# Sheet2.net
KiCad netlist of a schematic drawn in Altium Designer
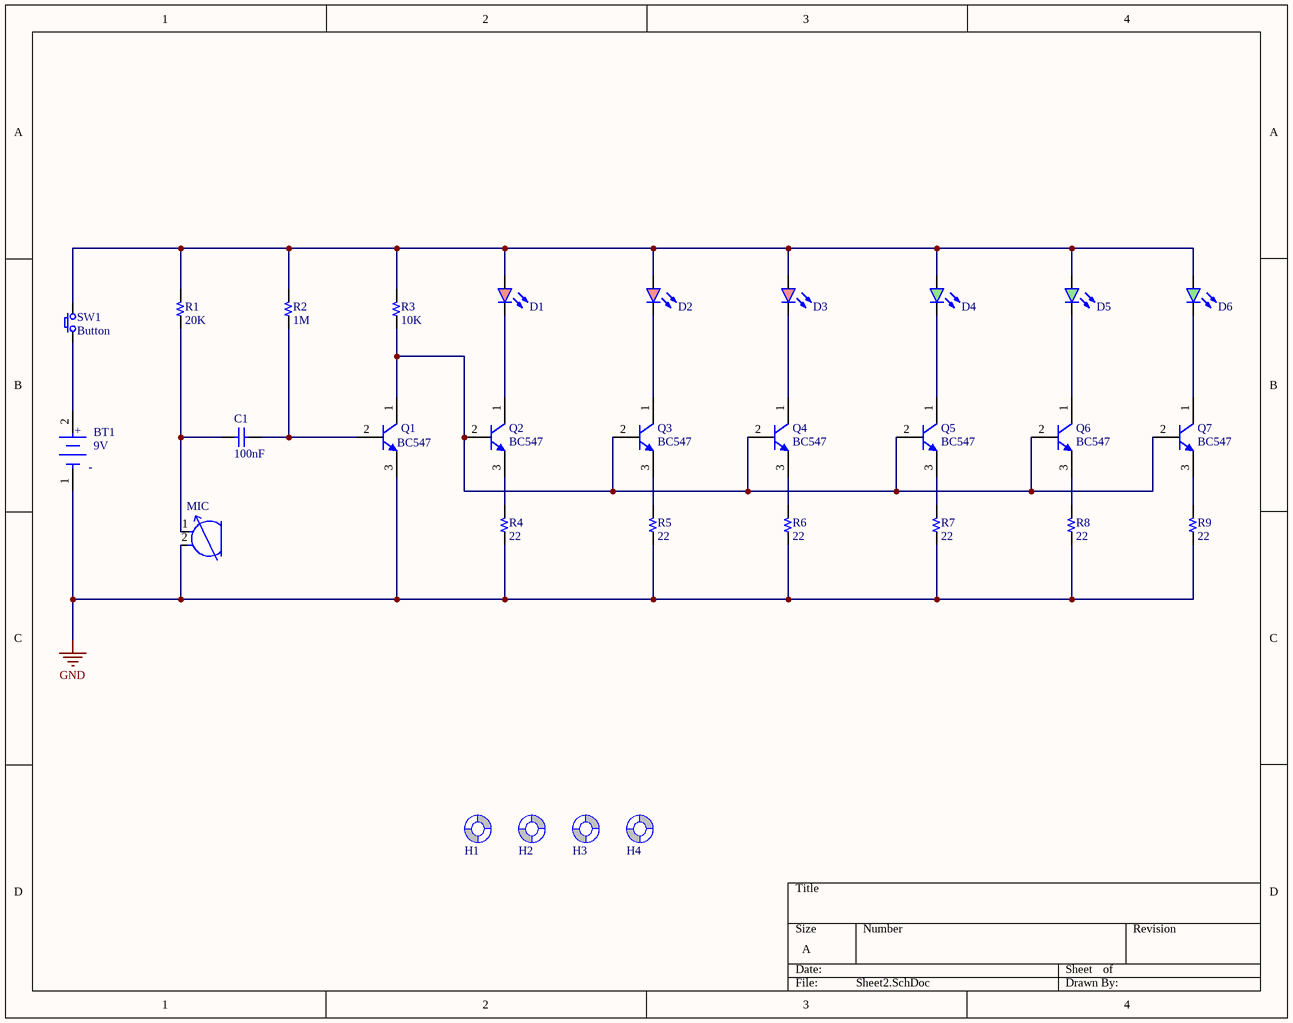
[diagram p0: Sheet2.SchDoc]

(export (version "E")
  (design (tool "Eeschema 10.0.6"))
  (components
    (comp (ref "BT1")
      (value "9V")
      (footprint "FP-BH9VPC-MFG")
      (description "BATTERY HOLDER 9V PC PIN")
      (fields
        (field (name "OCTOPART") "https://octopart.com/bh9vpc-memory+protection+devices-22788154")
        (field (name "MANUFACTURER PART NUMBER") "BH9VPC")
      )
      (libsource (lib "Altium Content Vault") (part "60d3b5b901a8747834971d0eb8cf3fd"))
    )
    (comp (ref "C1")
      (value "100nF")
      (footprint "CAP Ceramic/W300")
      (description "Capacitor non-pol")
      (libsource (lib "chipfc_libs") (part "Capacitor NP"))
    )
    (comp (ref "D1")
      (value "LED RED")
      (footprint "LED 10MM - RED")
      (description "Typical LED 3-pin 2-color")
      (libsource (lib "led") (part "LED RED"))
    )
    (comp (ref "D2")
      (value "LED RED")
      (footprint "LED 10MM - RED")
      (description "Typical LED 3-pin 2-color")
      (libsource (lib "led") (part "LED RED"))
    )
    (comp (ref "D3")
      (value "LED RED")
      (footprint "LED 10MM - RED")
      (description "Typical LED 3-pin 2-color")
      (libsource (lib "led") (part "LED RED"))
    )
    (comp (ref "D4")
      (value "LED GREEN")
      (footprint "LED 10MM - GREEN")
      (description "Typical LED 3-pin 2-color")
      (libsource (lib "led") (part "LED GREEN"))
    )
    (comp (ref "D5")
      (value "LED GREEN")
      (footprint "LED 10MM - GREEN")
      (description "Typical LED 3-pin 2-color")
      (libsource (lib "led") (part "LED GREEN"))
    )
    (comp (ref "D6")
      (value "LED GREEN")
      (footprint "LED 10MM - GREEN")
      (description "Typical LED 3-pin 2-color")
      (libsource (lib "led") (part "LED GREEN"))
    )
    (comp (ref "H1")
      (value "Screw Hole")
      (footprint "SCREW/3.2/7.0/M")
      (libsource (lib "chipfc_libs") (part "Screw Hole"))
    )
    (comp (ref "H2")
      (value "Screw Hole")
      (footprint "SCREW/3.2/7.0/M")
      (libsource (lib "chipfc_libs") (part "Screw Hole"))
    )
    (comp (ref "H3")
      (value "Screw Hole")
      (footprint "SCREW/3.2/7.0/M")
      (libsource (lib "chipfc_libs") (part "Screw Hole"))
    )
    (comp (ref "H4")
      (value "Screw Hole")
      (footprint "SCREW/3.2/7.0/M")
      (libsource (lib "chipfc_libs") (part "Screw Hole"))
    )
    (comp (ref "MIC")
      (value "POM-3535P-3-R")
      (footprint "FP-POM-3535P-3-R-MFG")
      (description "MIC COND ANALOG OMNI -35DB 6MM D")
      (libsource (lib "Altium Content Vault") (part "8932b53fa08aabe3022b5f676529f57"))
    )
    (comp (ref "Q1")
      (value "BC547")
      (footprint "ONSC-TO-92-3-29-11_AM_BL")
      (description "Amplifier Transistor, NPN Silicon, 3-Pin TO-92, Pb-Free, Tape and Reel")
      (fields (field (name "MANUFACTURER") "On Semiconductor") (field (name "PARTNUMBER") "BC547BRL1G"))
      (libsource (lib "Altium Content Vault") (part "ONSC-NPN-C1B2E3-3"))
    )
    (comp (ref "Q2")
      (value "BC547")
      (footprint "ONSC-TO-92-3-29-11_AM_BL")
      (description "Amplifier Transistor, NPN Silicon, 3-Pin TO-92, Pb-Free, Tape and Reel")
      (fields (field (name "MANUFACTURER") "On Semiconductor") (field (name "PARTNUMBER") "BC547BRL1G"))
      (libsource (lib "Altium Content Vault") (part "ONSC-NPN-C1B2E3-3"))
    )
    (comp (ref "Q3")
      (value "BC547")
      (footprint "ONSC-TO-92-3-29-11_AM_BL")
      (description "Amplifier Transistor, NPN Silicon, 3-Pin TO-92, Pb-Free, Tape and Reel")
      (fields (field (name "MANUFACTURER") "On Semiconductor") (field (name "PARTNUMBER") "BC547BRL1G"))
      (libsource (lib "Altium Content Vault") (part "ONSC-NPN-C1B2E3-3"))
    )
    (comp (ref "Q4")
      (value "BC547")
      (footprint "ONSC-TO-92-3-29-11_AM_BL")
      (description "Amplifier Transistor, NPN Silicon, 3-Pin TO-92, Pb-Free, Tape and Reel")
      (fields (field (name "MANUFACTURER") "On Semiconductor") (field (name "PARTNUMBER") "BC547BRL1G"))
      (libsource (lib "Altium Content Vault") (part "ONSC-NPN-C1B2E3-3"))
    )
    (comp (ref "Q5")
      (value "BC547")
      (footprint "ONSC-TO-92-3-29-11_AM_BL")
      (description "Amplifier Transistor, NPN Silicon, 3-Pin TO-92, Pb-Free, Tape and Reel")
      (fields (field (name "MANUFACTURER") "On Semiconductor") (field (name "PARTNUMBER") "BC547BRL1G"))
      (libsource (lib "Altium Content Vault") (part "ONSC-NPN-C1B2E3-3"))
    )
    (comp (ref "Q6")
      (value "BC547")
      (footprint "ONSC-TO-92-3-29-11_AM_BL")
      (description "Amplifier Transistor, NPN Silicon, 3-Pin TO-92, Pb-Free, Tape and Reel")
      (fields (field (name "MANUFACTURER") "On Semiconductor") (field (name "PARTNUMBER") "BC547BRL1G"))
      (libsource (lib "Altium Content Vault") (part "ONSC-NPN-C1B2E3-3"))
    )
    (comp (ref "Q7")
      (value "BC547")
      (footprint "ONSC-TO-92-3-29-11_AM_BL")
      (description "Amplifier Transistor, NPN Silicon, 3-Pin TO-92, Pb-Free, Tape and Reel")
      (fields (field (name "MANUFACTURER") "On Semiconductor") (field (name "PARTNUMBER") "BC547BRL1G"))
      (libsource (lib "Altium Content Vault") (part "ONSC-NPN-C1B2E3-3"))
    )
    (comp (ref "R1")
      (value "20K")
      (footprint "R 1/4W/300")
      (description "Resistor")
      (libsource (lib "chipfc_libs") (part "Resistor"))
    )
    (comp (ref "R2")
      (value "1M")
      (footprint "R 1/4W/300")
      (description "Resistor")
      (libsource (lib "chipfc_libs") (part "Resistor"))
    )
    (comp (ref "R3")
      (value "10K")
      (footprint "R 1/4W/300")
      (description "Resistor")
      (libsource (lib "chipfc_libs") (part "Resistor"))
    )
    (comp (ref "R4")
      (value "22")
      (footprint "R 1/4W/300")
      (description "Resistor")
      (libsource (lib "chipfc_libs") (part "Resistor"))
    )
    (comp (ref "R5")
      (value "22")
      (footprint "R 1/4W/300")
      (description "Resistor")
      (libsource (lib "chipfc_libs") (part "Resistor"))
    )
    (comp (ref "R6")
      (value "22")
      (footprint "R 1/4W/300")
      (description "Resistor")
      (libsource (lib "chipfc_libs") (part "Resistor"))
    )
    (comp (ref "R7")
      (value "22")
      (footprint "R 1/4W/300")
      (description "Resistor")
      (libsource (lib "chipfc_libs") (part "Resistor"))
    )
    (comp (ref "R8")
      (value "22")
      (footprint "R 1/4W/300")
      (description "Resistor")
      (libsource (lib "chipfc_libs") (part "Resistor"))
    )
    (comp (ref "R9")
      (value "22")
      (footprint "R 1/4W/300")
      (description "Resistor")
      (libsource (lib "chipfc_libs") (part "Resistor"))
    )
    (comp (ref "SW1")
      (value "Button")
      (footprint "SW/2/DIP")
      (description "Tact switch 2 pin")
      (libsource (lib "chipfc_libs") (part "SW SPST"))
    )
  )
  (nets
    (net (code "1") (name "GND") (class "Default")
      (node (ref "BT1") (pin "1") (pinfunction "C_1") (pintype "passive"))
      (node (ref "MIC") (pin "2") (pinfunction "C_2") (pintype "passive"))
      (node (ref "Q1") (pin "3") (pinfunction "E_3") (pintype "passive"))
      (node (ref "R4") (pin "1") (pinfunction "1_1") (pintype "passive"))
      (node (ref "R5") (pin "1") (pinfunction "1_1") (pintype "passive"))
      (node (ref "R6") (pin "1") (pinfunction "1_1") (pintype "passive"))
      (node (ref "R7") (pin "1") (pinfunction "1_1") (pintype "passive"))
      (node (ref "R8") (pin "1") (pinfunction "1_1") (pintype "passive"))
      (node (ref "R9") (pin "1") (pinfunction "1_1") (pintype "passive"))
    )
    (net (code "2") (name "Net-(BT1-A)") (class "Default")
      (node (ref "BT1") (pin "2") (pinfunction "A_2") (pintype "passive"))
      (node (ref "SW1") (pin "1") (pinfunction "1_1") (pintype "passive"))
    )
    (net (code "3") (name "Net-(D1-A)") (class "Default")
      (node (ref "D1") (pin "1") (pinfunction "A_1") (pintype "passive"))
      (node (ref "D2") (pin "1") (pinfunction "A_1") (pintype "passive"))
      (node (ref "D3") (pin "1") (pinfunction "A_1") (pintype "passive"))
      (node (ref "D4") (pin "1") (pinfunction "A_1") (pintype "passive"))
      (node (ref "D5") (pin "1") (pinfunction "A_1") (pintype "passive"))
      (node (ref "D6") (pin "1") (pinfunction "A_1") (pintype "passive"))
      (node (ref "R1") (pin "2") (pinfunction "2_2") (pintype "passive"))
      (node (ref "R2") (pin "2") (pinfunction "2_2") (pintype "passive"))
      (node (ref "R3") (pin "2") (pinfunction "2_2") (pintype "passive"))
      (node (ref "SW1") (pin "2") (pinfunction "2_2") (pintype "passive"))
    )
    (net (code "4") (name "Net-(D1-K)") (class "Default")
      (node (ref "D1") (pin "2") (pinfunction "K_2") (pintype "passive"))
      (node (ref "Q2") (pin "1") (pinfunction "C_1") (pintype "passive"))
    )
    (net (code "5") (name "Net-(D2-K)") (class "Default")
      (node (ref "D2") (pin "2") (pinfunction "K_2") (pintype "passive"))
      (node (ref "Q3") (pin "1") (pinfunction "C_1") (pintype "passive"))
    )
    (net (code "6") (name "Net-(D3-K)") (class "Default")
      (node (ref "D3") (pin "2") (pinfunction "K_2") (pintype "passive"))
      (node (ref "Q4") (pin "1") (pinfunction "C_1") (pintype "passive"))
    )
    (net (code "7") (name "Net-(D4-K)") (class "Default")
      (node (ref "D4") (pin "2") (pinfunction "K_2") (pintype "passive"))
      (node (ref "Q5") (pin "1") (pinfunction "C_1") (pintype "passive"))
    )
    (net (code "8") (name "Net-(D5-K)") (class "Default")
      (node (ref "D5") (pin "2") (pinfunction "K_2") (pintype "passive"))
      (node (ref "Q6") (pin "1") (pinfunction "C_1") (pintype "passive"))
    )
    (net (code "9") (name "Net-(D6-K)") (class "Default")
      (node (ref "D6") (pin "2") (pinfunction "K_2") (pintype "passive"))
      (node (ref "Q7") (pin "1") (pinfunction "C_1") (pintype "passive"))
    )
    (net (code "10") (name "Net-(MIC-A)") (class "Default")
      (node (ref "C1") (pin "1") (pinfunction "1_1") (pintype "passive"))
      (node (ref "MIC") (pin "1") (pinfunction "A_1") (pintype "passive"))
      (node (ref "R1") (pin "1") (pinfunction "1_1") (pintype "passive"))
    )
    (net (code "11") (name "Net-(Q1-B)") (class "Default")
      (node (ref "C1") (pin "2") (pinfunction "2_2") (pintype "passive"))
      (node (ref "Q1") (pin "2") (pinfunction "B_2") (pintype "passive"))
      (node (ref "R2") (pin "1") (pinfunction "1_1") (pintype "passive"))
    )
    (net (code "12") (name "Net-(Q1-C)") (class "Default")
      (node (ref "Q1") (pin "1") (pinfunction "C_1") (pintype "passive"))
      (node (ref "Q2") (pin "2") (pinfunction "B_2") (pintype "passive"))
      (node (ref "Q3") (pin "2") (pinfunction "B_2") (pintype "passive"))
      (node (ref "Q4") (pin "2") (pinfunction "B_2") (pintype "passive"))
      (node (ref "Q5") (pin "2") (pinfunction "B_2") (pintype "passive"))
      (node (ref "Q6") (pin "2") (pinfunction "B_2") (pintype "passive"))
      (node (ref "Q7") (pin "2") (pinfunction "B_2") (pintype "passive"))
      (node (ref "R3") (pin "1") (pinfunction "1_1") (pintype "passive"))
    )
    (net (code "13") (name "Net-(Q2-E)") (class "Default")
      (node (ref "Q2") (pin "3") (pinfunction "E_3") (pintype "passive"))
      (node (ref "R4") (pin "2") (pinfunction "2_2") (pintype "passive"))
    )
    (net (code "14") (name "Net-(Q3-E)") (class "Default")
      (node (ref "Q3") (pin "3") (pinfunction "E_3") (pintype "passive"))
      (node (ref "R5") (pin "2") (pinfunction "2_2") (pintype "passive"))
    )
    (net (code "15") (name "Net-(Q4-E)") (class "Default")
      (node (ref "Q4") (pin "3") (pinfunction "E_3") (pintype "passive"))
      (node (ref "R6") (pin "2") (pinfunction "2_2") (pintype "passive"))
    )
    (net (code "16") (name "Net-(Q5-E)") (class "Default")
      (node (ref "Q5") (pin "3") (pinfunction "E_3") (pintype "passive"))
      (node (ref "R7") (pin "2") (pinfunction "2_2") (pintype "passive"))
    )
    (net (code "17") (name "Net-(Q6-E)") (class "Default")
      (node (ref "Q6") (pin "3") (pinfunction "E_3") (pintype "passive"))
      (node (ref "R8") (pin "2") (pinfunction "2_2") (pintype "passive"))
    )
    (net (code "18") (name "Net-(Q7-E)") (class "Default")
      (node (ref "Q7") (pin "3") (pinfunction "E_3") (pintype "passive"))
      (node (ref "R9") (pin "2") (pinfunction "2_2") (pintype "passive"))
    )
    (net (code "19") (name "unconnected-(H1-Screw-Pad1)") (class "Default")
      (node (ref "H1") (pin "1") (pinfunction "Screw_1") (pintype "passive"))
    )
    (net (code "20") (name "unconnected-(H2-Screw-Pad1)") (class "Default")
      (node (ref "H2") (pin "1") (pinfunction "Screw_1") (pintype "passive"))
    )
    (net (code "21") (name "unconnected-(H3-Screw-Pad1)") (class "Default")
      (node (ref "H3") (pin "1") (pinfunction "Screw_1") (pintype "passive"))
    )
    (net (code "22") (name "unconnected-(H4-Screw-Pad1)") (class "Default")
      (node (ref "H4") (pin "1") (pinfunction "Screw_1") (pintype "passive"))
    )
  )
)
